# MainPCB.net
KiCad netlist of a schematic drawn in Altium Designer
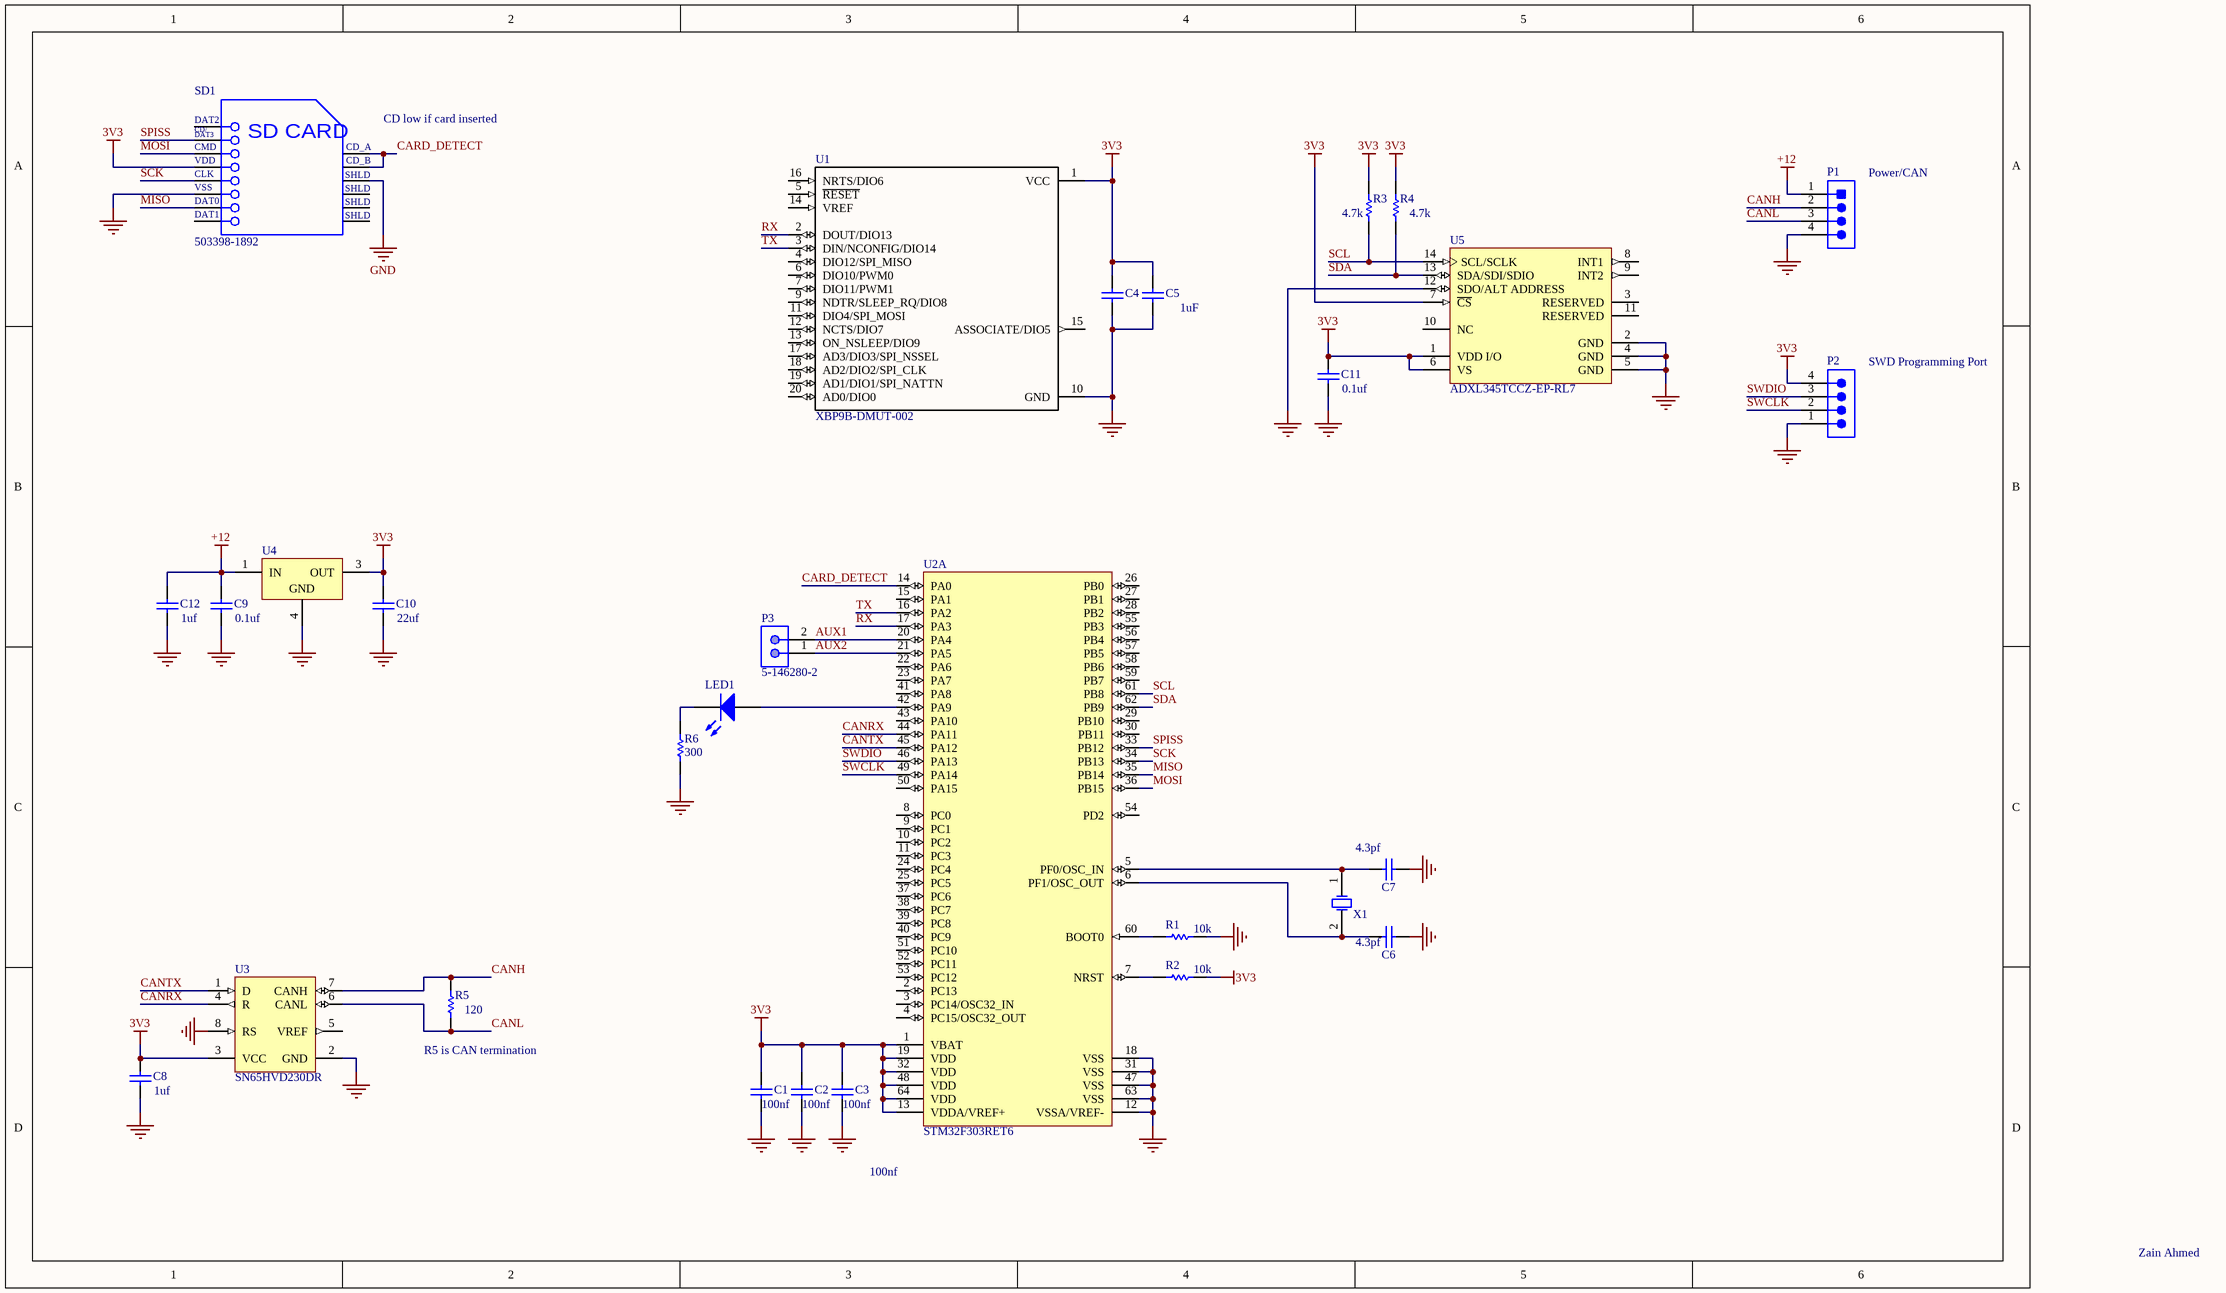
[diagram p0: MainPCB.SchDoc]

(export (version "E")
  (design (tool "Eeschema 10.0.6"))
  (components
    (comp (ref "C1")
      (value "C0402C104K8PAC7867")
      (footprint "CAPC1005X60X30ML05T10")
      (fields (field (name "MANUFACTURER") "Kemet"))
      (libsource (lib "Altium Content Vault") (part "CAP"))
    )
    (comp (ref "C2")
      (value "C0402C104K8PAC7867")
      (footprint "CAPC1005X60X30ML05T10")
      (fields (field (name "MANUFACTURER") "Kemet"))
      (libsource (lib "Altium Content Vault") (part "CAP"))
    )
    (comp (ref "C3")
      (value "C0402C104K8PAC7867")
      (footprint "CAPC1005X60X30ML05T10")
      (fields (field (name "MANUFACTURER") "Kemet"))
      (libsource (lib "Altium Content Vault") (part "CAP"))
    )
    (comp (ref "C4")
      (value "12065C105KAT2A")
      (footprint "CAPC3216X180X50LL20T25")
      (description "Chip Capacitor, 1 uF, +/- 10%, 50 V, -55 to 125 degC, 1206 (3216 Metric), RoHS, Tape and Reel")
      (fields (field (name "MANUFACTURER") "AVX"))
      (libsource (lib "Altium Content Vault") (part "CAP-NP-2"))
    )
    (comp (ref "C5")
      (value "12065C105KAT2A")
      (footprint "CAPC3216X180X50LL20T25")
      (description "Chip Capacitor, 1 uF, +/- 10%, 50 V, -55 to 125 degC, 1206 (3216 Metric), RoHS, Tape and Reel")
      (fields (field (name "MANUFACTURER") "AVX"))
      (libsource (lib "Altium Content Vault") (part "CAP-NP-2"))
    )
    (comp (ref "C6")
      (value "CAP 4.3pF 50V 0402(1005)")
      (footprint "CAPC0402(1005)60_M")
      (description "CAP 4.3pF 50V ±0.25pF 0402 (1005 Metric) Thickness 0.6mm SMD")
      (fields (field (name "TOLERANCE") "Â±0.25pF"))
      (libsource (lib "Altium Content Vault") (part "CAP"))
    )
    (comp (ref "C7")
      (value "CAP 4.3pF 50V 0402(1005)")
      (footprint "CAPC0402(1005)60_M")
      (description "CAP 4.3pF 50V ±0.25pF 0402 (1005 Metric) Thickness 0.6mm SMD")
      (fields (field (name "TOLERANCE") "Â±0.25pF"))
      (libsource (lib "Altium Content Vault") (part "CAP"))
    )
    (comp (ref "C8")
      (value "C1206C105K3RACTU")
      (footprint "CAPC3216X180X50ML20T25")
      (description "Chip Capacitor, 1 uF, +/- 10%, 25 V, -55 to 125 degC, 1206 (3216 Metric), RoHS, Tape and Reel")
      (fields (field (name "MANUFACTURER") "Kemet") (field (name "TOLERANCE") "10%"))
      (libsource (lib "Altium Content Vault") (part "CAP-NP-2"))
    )
    (comp (ref "C9")
      (value "GRM188R71H104KA93D")
      (footprint "CAPC1608X90X35ML10T15")
      (description "Chip Capacitor, 0.1 uF, +/- 10%, 50 V, -55 to 125 degC, 0603 (1608 Metric), RoHS, Tape and Reel")
      (fields (field (name "TOLERANCE") "10%") (field (name "VOLTAGE") "50V"))
      (libsource (lib "Altium Content Vault") (part "CAP-NP-2"))
    )
    (comp (ref "C10")
      (value "GRM188R61A226ME15D")
      (footprint "CAPC1608X100X38LL20T18")
      (description "Chip Capacitor, 22 uF, +/- 20%, 10 V, -55 to 85 degC, 0603 (1608 Metric), RoHS, Tape and Reel")
      (fields (field (name "MANUFACTURER") "Murata") (field (name "TOLERANCE") "20%"))
      (libsource (lib "Altium Content Vault") (part "CAP-NP-2"))
    )
    (comp (ref "C11")
      (value "GRM188R71H104KA93D")
      (footprint "CAPC1608X90X35ML10T15")
      (description "Chip Capacitor, 0.1 uF, +/- 10%, 50 V, -55 to 125 degC, 0603 (1608 Metric), RoHS, Tape and Reel")
      (fields (field (name "TOLERANCE") "10%") (field (name "VOLTAGE") "50V"))
      (libsource (lib "Altium Content Vault") (part "CAP-NP-2"))
    )
    (comp (ref "C12")
      (value "GRM155R61A105KE15D")
      (footprint "CAPC1005X55X25NL05T10")
      (fields (field (name "MANUFACTURER") "Murata"))
      (libsource (lib "Altium Content Vault") (part "CAP"))
    )
    (comp (ref "LED1")
      (value "150120BS75000")
      (footprint "1206_A")
      (description "SMD mono-color Chip LED, WL-SMCW, Blue")
      (fields (field (name "MANUFACTURER") "Wuerth Elektronik"))
      (libsource (lib "Altium Content Vault") (part "WE-LED_K1A2-2"))
    )
    (comp (ref "P1")
      (value "B4B-PH-K-S(LF)(SN)")
      (footprint "JST-B4B-PH-K-S_V")
      (fields (field (name "MANUFACTURER") "JST"))
      (libsource (lib "Altium Content Vault") (part "CN-1P-M-R4"))
    )
    (comp (ref "P2")
      (value "TSW-104-08-T-S")
      (footprint "SMTC-TSW-104-08-X-S")
      (description "0.025\" SQ Post Header, Through-hole, Vertical, -55 to 105 degC, 2.54 mm Pitch, 4-Pin, Male, RoHS")
      (fields (field (name "MANUFACTURER") "Samtec"))
      (libsource (lib "Altium Content Vault") (part "SMTC-TSW-104-08-X-S"))
    )
    (comp (ref "P3")
      (value "5-146280-2")
      (footprint "TECO-5-146280-2_V")
      (fields (field (name "MANUFACTURER") "TE Connectivity"))
      (libsource (lib "Altium Content Vault") (part "CN-1P-M-R2"))
    )
    (comp (ref "R1")
      (value "ERA8AEB103V")
      (footprint "RESC3216X70X50LL20T25")
      (fields (field (name "MANUFACTURER") "Panasonic"))
      (libsource (lib "Altium Content Vault") (part "RES"))
    )
    (comp (ref "R2")
      (value "ERA8AEB103V")
      (footprint "RESC3216X70X50LL20T25")
      (fields (field (name "MANUFACTURER") "Panasonic"))
      (libsource (lib "Altium Content Vault") (part "RES"))
    )
    (comp (ref "R3")
      (value "ERA6AEB472V")
      (footprint "RESC2013X60X40ML20T25")
      (fields (field (name "MANUFACTURER") "Panasonic"))
      (libsource (lib "Altium Content Vault") (part "RES"))
    )
    (comp (ref "R4")
      (value "ERA6AEB472V")
      (footprint "RESC2013X60X40ML20T25")
      (fields (field (name "MANUFACTURER") "Panasonic"))
      (libsource (lib "Altium Content Vault") (part "RES"))
    )
    (comp (ref "R5")
      (value "CRCW1206120RFKEA")
      (footprint "RESC3216X60X45LL10T20")
      (fields (field (name "MANUFACTURER") "Vishay Dale"))
      (libsource (lib "Altium Content Vault") (part "RES"))
    )
    (comp (ref "R6")
      (value "300")
      (footprint "RESC3216X70X50NL05T20")
      (fields (field (name "MANUFACTURER") "Panasonic") (field (name "PART NUMBER") "ERJ8ENF3000V"))
      (libsource (lib "Altium Content Vault") (part "RES"))
    )
    (comp (ref "SD1")
      (value "503398-1892")
      (footprint "MOLX-503398-1892_V")
      (description "Micro SD Connector, Pitch 1.1 mm, 8 Position, Height 1.4 mm, -25 to 85 degC, RoHS, Tape and Reel")
      (fields (field (name "MANUFACTURER") "Molex"))
      (libsource (lib "Altium Content Vault") (part "CN-SD-8-2SW-4S"))
    )
    (comp (ref "U1")
      (value "XBP9B-DMUT-002")
      (footprint "*DIP2200W51P200L3294H279Q20P")
      (description "XBee-PRO 900HP DigiMesh 900 MHz 200 Kbps RF Module with U.FL Connector")
      (fields (field (name "MF") "Digi International"))
      (libsource (lib "XBP9B-DMUT-002") (part "XBP9B-DMUT-002"))
    )
    (comp (ref "U2A")
      (value "STM32F303RET6")
      (footprint "STM-LQFP64_L")
      (libsource (lib "Altium Content Vault") (part "MC-ARM-STM32F303-LQFP64"))
    )
    (comp (ref "U3")
      (value "SN65HVD230DR")
      (footprint "D0008A_L")
      (fields (field (name "MANUFACTURER") "Texas Instruments"))
      (libsource (lib "Altium Content Vault") (part "TI-SN65HVD230-SOIC_D-8"))
    )
    (comp (ref "U4")
      (value "TL760M33QKVURQ1")
      (footprint "KVU0003A_M")
      (fields (field (name "MANUFACTURER") "Texas Instruments"))
      (libsource (lib "Altium Content Vault") (part "TI-TL7X0MXX-Q1KVU3"))
    )
    (comp (ref "U5")
      (value "ADXL345TCCZ-EP-RL7")
      (footprint "ADI-CC-14-1_V")
      (fields (field (name "MANUFACTURER") "Analog Devices"))
      (libsource (lib "Altium Content Vault") (part "ADI-ADXL34X-CC-14-1"))
    )
    (comp (ref "X1")
      (value "ABM3-8.000MHZ-D2Y-T")
      (footprint "ABRA-ABM3-2_V")
      (description "Miniature Ceramic Crystal, 8 MHz, -40 to 85 degC, 2-Pin SMD, RoHS, Tape and Reel")
      (fields (field (name "MANUFACTURER") "ABRACON") (field (name "TOLERANCE") "20PPM"))
      (libsource (lib "Altium Content Vault") (part "XTAL_1-2-2"))
    )
  )
  (nets
    (net (code "1") (name "+12") (class "Default")
      (node (ref "C12") (pin "1") (pinfunction "1_1") (pintype "passive"))
      (node (ref "C9") (pin "1") (pinfunction "1_1") (pintype "passive"))
      (node (ref "P1") (pin "1") (pinfunction "1_1") (pintype "passive"))
      (node (ref "U4") (pin "1") (pinfunction "IN_1") (pintype "power_in"))
    )
    (net (code "2") (name "/AUX1") (class "Default")
      (node (ref "P3") (pin "2") (pinfunction "2_2") (pintype "passive"))
      (node (ref "U2A") (pin "20") (pinfunction "PA4_20") (pintype "bidirectional"))
    )
    (net (code "3") (name "/AUX2") (class "Default")
      (node (ref "P3") (pin "1") (pinfunction "1_1") (pintype "passive"))
      (node (ref "U2A") (pin "21") (pinfunction "PA5_21") (pintype "bidirectional"))
    )
    (net (code "4") (name "/CANH") (class "Default")
      (node (ref "P1") (pin "2") (pinfunction "2_2") (pintype "passive"))
      (node (ref "R5") (pin "1") (pinfunction "1_1") (pintype "passive"))
      (node (ref "U3") (pin "7") (pinfunction "CANH_7") (pintype "bidirectional"))
    )
    (net (code "5") (name "/CANL") (class "Default")
      (node (ref "P1") (pin "3") (pinfunction "3_3") (pintype "passive"))
      (node (ref "R5") (pin "2") (pinfunction "2_2") (pintype "passive"))
      (node (ref "U3") (pin "6") (pinfunction "CANL_6") (pintype "bidirectional"))
    )
    (net (code "6") (name "/CANRX") (class "Default")
      (node (ref "U2A") (pin "44") (pinfunction "PA11_44") (pintype "bidirectional"))
      (node (ref "U3") (pin "4") (pinfunction "R_4") (pintype "output"))
    )
    (net (code "7") (name "/CANTX") (class "Default")
      (node (ref "U2A") (pin "45") (pinfunction "PA12_45") (pintype "bidirectional"))
      (node (ref "U3") (pin "1") (pinfunction "D_1") (pintype "input"))
    )
    (net (code "8") (name "/CARD_DETECT") (class "Default")
      (node (ref "SD1") (pin "10") (pinfunction "CD_B_10") (pintype "passive"))
      (node (ref "SD1") (pin "9") (pinfunction "CD_A_9") (pintype "passive"))
      (node (ref "U2A") (pin "14") (pinfunction "PA0_14") (pintype "bidirectional"))
    )
    (net (code "9") (name "/MISO") (class "Default")
      (node (ref "SD1") (pin "7") (pinfunction "DAT0_7") (pintype "passive"))
      (node (ref "U2A") (pin "35") (pinfunction "PB14_35") (pintype "bidirectional"))
    )
    (net (code "10") (name "/MOSI") (class "Default")
      (node (ref "SD1") (pin "3") (pinfunction "CMD_3") (pintype "passive"))
      (node (ref "U2A") (pin "36") (pinfunction "PB15_36") (pintype "bidirectional"))
    )
    (net (code "11") (name "/RX") (class "Default")
      (node (ref "U1") (pin "2") (pinfunction "DOUT/DIO13_2") (pintype "bidirectional"))
      (node (ref "U2A") (pin "17") (pinfunction "PA3_17") (pintype "bidirectional"))
    )
    (net (code "12") (name "/SCK") (class "Default")
      (node (ref "SD1") (pin "5") (pinfunction "CLK_5") (pintype "passive"))
      (node (ref "U2A") (pin "34") (pinfunction "PB13_34") (pintype "bidirectional"))
    )
    (net (code "13") (name "/SCL") (class "Default")
      (node (ref "R3") (pin "2") (pinfunction "2_2") (pintype "passive"))
      (node (ref "U2A") (pin "61") (pinfunction "PB8_61") (pintype "bidirectional"))
      (node (ref "U5") (pin "14") (pinfunction "SCL/SCLK_14") (pintype "input"))
    )
    (net (code "14") (name "/SDA") (class "Default")
      (node (ref "R4") (pin "2") (pinfunction "2_2") (pintype "passive"))
      (node (ref "U2A") (pin "62") (pinfunction "PB9_62") (pintype "bidirectional"))
      (node (ref "U5") (pin "13") (pinfunction "SDA/SDI/SDIO_13") (pintype "bidirectional"))
    )
    (net (code "15") (name "/SPISS") (class "Default")
      (node (ref "SD1") (pin "2") (pinfunction "CD/DAT3_2") (pintype "passive"))
      (node (ref "U2A") (pin "33") (pinfunction "PB12_33") (pintype "bidirectional"))
    )
    (net (code "16") (name "/SWCLK") (class "Default")
      (node (ref "P2") (pin "2") (pinfunction "2_2") (pintype "passive"))
      (node (ref "U2A") (pin "49") (pinfunction "PA14_49") (pintype "bidirectional"))
    )
    (net (code "17") (name "/SWDIO") (class "Default")
      (node (ref "P2") (pin "3") (pinfunction "3_3") (pintype "passive"))
      (node (ref "U2A") (pin "46") (pinfunction "PA13_46") (pintype "bidirectional"))
    )
    (net (code "18") (name "/TX") (class "Default")
      (node (ref "U1") (pin "3") (pinfunction "DIN/NCONFIG/DIO14_3") (pintype "bidirectional"))
      (node (ref "U2A") (pin "16") (pinfunction "PA2_16") (pintype "bidirectional"))
    )
    (net (code "19") (name "3V3") (class "Default")
      (node (ref "C1") (pin "1") (pinfunction "1_1") (pintype "passive"))
      (node (ref "C10") (pin "1") (pinfunction "1_1") (pintype "passive"))
      (node (ref "C11") (pin "1") (pinfunction "1_1") (pintype "passive"))
      (node (ref "C2") (pin "1") (pinfunction "1_1") (pintype "passive"))
      (node (ref "C3") (pin "1") (pinfunction "1_1") (pintype "passive"))
      (node (ref "C4") (pin "1") (pinfunction "1_1") (pintype "passive"))
      (node (ref "C5") (pin "1") (pinfunction "1_1") (pintype "passive"))
      (node (ref "C8") (pin "1") (pinfunction "1_1") (pintype "passive"))
      (node (ref "P2") (pin "4") (pinfunction "4_4") (pintype "passive"))
      (node (ref "R2") (pin "2") (pinfunction "2_2") (pintype "passive"))
      (node (ref "R3") (pin "1") (pinfunction "1_1") (pintype "passive"))
      (node (ref "R4") (pin "1") (pinfunction "1_1") (pintype "passive"))
      (node (ref "SD1") (pin "4") (pinfunction "VDD_4") (pintype "passive"))
      (node (ref "U1") (pin "1") (pinfunction "VCC_1") (pintype "power_in"))
      (node (ref "U2A") (pin "1") (pinfunction "VBAT_1") (pintype "power_in"))
      (node (ref "U2A") (pin "13") (pinfunction "VDDA/VREF+_13") (pintype "power_in"))
      (node (ref "U2A") (pin "19") (pinfunction "VDD_19") (pintype "power_in"))
      (node (ref "U2A") (pin "32") (pinfunction "VDD_32") (pintype "power_in"))
      (node (ref "U2A") (pin "48") (pinfunction "VDD_48") (pintype "power_in"))
      (node (ref "U2A") (pin "64") (pinfunction "VDD_64") (pintype "power_in"))
      (node (ref "U3") (pin "3") (pinfunction "VCC_3") (pintype "power_in"))
      (node (ref "U4") (pin "3") (pinfunction "OUT_3") (pintype "power_in"))
      (node (ref "U5") (pin "1") (pinfunction "VDD_I/O_1") (pintype "power_in"))
      (node (ref "U5") (pin "6") (pinfunction "VS_6") (pintype "power_in"))
      (node (ref "U5") (pin "7") (pinfunction "~{CS}_7") (pintype "input"))
    )
    (net (code "20") (name "GND") (class "Default")
      (node (ref "C1") (pin "2") (pinfunction "2_2") (pintype "passive"))
      (node (ref "C10") (pin "2") (pinfunction "2_2") (pintype "passive"))
      (node (ref "C11") (pin "2") (pinfunction "2_2") (pintype "passive"))
      (node (ref "C12") (pin "2") (pinfunction "2_2") (pintype "passive"))
      (node (ref "C2") (pin "2") (pinfunction "2_2") (pintype "passive"))
      (node (ref "C3") (pin "2") (pinfunction "2_2") (pintype "passive"))
      (node (ref "C4") (pin "2") (pinfunction "2_2") (pintype "passive"))
      (node (ref "C5") (pin "2") (pinfunction "2_2") (pintype "passive"))
      (node (ref "C6") (pin "1") (pinfunction "1_1") (pintype "passive"))
      (node (ref "C7") (pin "1") (pinfunction "1_1") (pintype "passive"))
      (node (ref "C8") (pin "2") (pinfunction "2_2") (pintype "passive"))
      (node (ref "C9") (pin "2") (pinfunction "2_2") (pintype "passive"))
      (node (ref "P1") (pin "4") (pinfunction "4_4") (pintype "passive"))
      (node (ref "P2") (pin "1") (pinfunction "1_1") (pintype "passive"))
      (node (ref "R1") (pin "2") (pinfunction "2_2") (pintype "passive"))
      (node (ref "R6") (pin "2") (pinfunction "2_2") (pintype "passive"))
      (node (ref "SD1") (pin "11") (pinfunction "SHLD_11") (pintype "passive"))
      (node (ref "SD1") (pin "6") (pinfunction "VSS_6") (pintype "passive"))
      (node (ref "U1") (pin "10") (pinfunction "GND_10") (pintype "power_in"))
      (node (ref "U2A") (pin "12") (pinfunction "VSSA/VREF-_12") (pintype "power_in"))
      (node (ref "U2A") (pin "18") (pinfunction "VSS_18") (pintype "power_in"))
      (node (ref "U2A") (pin "31") (pinfunction "VSS_31") (pintype "power_in"))
      (node (ref "U2A") (pin "47") (pinfunction "VSS_47") (pintype "power_in"))
      (node (ref "U2A") (pin "63") (pinfunction "VSS_63") (pintype "power_in"))
      (node (ref "U3") (pin "2") (pinfunction "GND_2") (pintype "power_in"))
      (node (ref "U3") (pin "8") (pinfunction "RS_8") (pintype "input"))
      (node (ref "U4") (pin "4") (pinfunction "GND_4") (pintype "power_in"))
      (node (ref "U5") (pin "12") (pinfunction "SDO/ALT_ADDRESS_12") (pintype "bidirectional"))
      (node (ref "U5") (pin "2") (pinfunction "GND_2") (pintype "power_in"))
      (node (ref "U5") (pin "4") (pinfunction "GND_4") (pintype "power_in"))
      (node (ref "U5") (pin "5") (pinfunction "GND_5") (pintype "power_in"))
    )
    (net (code "21") (name "Net-(LED1-A)") (class "Default")
      (node (ref "LED1") (pin "2") (pinfunction "A_2") (pintype "passive"))
      (node (ref "U2A") (pin "42") (pinfunction "PA9_42") (pintype "bidirectional"))
    )
    (net (code "22") (name "Net-(LED1-K)") (class "Default")
      (node (ref "LED1") (pin "1") (pinfunction "K_1") (pintype "passive"))
      (node (ref "R6") (pin "1") (pinfunction "1_1") (pintype "passive"))
    )
    (net (code "23") (name "Net-(U2A-BOOT0)") (class "Default")
      (node (ref "R1") (pin "1") (pinfunction "1_1") (pintype "passive"))
      (node (ref "U2A") (pin "60") (pinfunction "BOOT0_60") (pintype "input"))
    )
    (net (code "24") (name "Net-(U2A-NRST)") (class "Default")
      (node (ref "R2") (pin "1") (pinfunction "1_1") (pintype "passive"))
      (node (ref "U2A") (pin "7") (pinfunction "NRST_7") (pintype "bidirectional"))
    )
    (net (code "25") (name "Net-(U2A-PF0{slash}OSC_IN)") (class "Default")
      (node (ref "C7") (pin "2") (pinfunction "2_2") (pintype "passive"))
      (node (ref "U2A") (pin "5") (pinfunction "PF0/OSC_IN_5") (pintype "bidirectional"))
      (node (ref "X1") (pin "1") (pinfunction "X1_1") (pintype "passive"))
    )
    (net (code "26") (name "Net-(U2A-PF1{slash}OSC_OUT)") (class "Default")
      (node (ref "C6") (pin "2") (pinfunction "2_2") (pintype "passive"))
      (node (ref "U2A") (pin "6") (pinfunction "PF1/OSC_OUT_6") (pintype "bidirectional"))
      (node (ref "X1") (pin "2") (pinfunction "X2_2") (pintype "passive"))
    )
    (net (code "27") (name "unconnected-(SD1-DAT1-Pad8)") (class "Default")
      (node (ref "SD1") (pin "8") (pinfunction "DAT1_8") (pintype "passive"))
    )
    (net (code "28") (name "unconnected-(SD1-DAT2-Pad1)") (class "Default")
      (node (ref "SD1") (pin "1") (pinfunction "DAT2_1") (pintype "passive"))
    )
    (net (code "29") (name "unconnected-(SD1-SHLD-Pad12)") (class "Default")
      (node (ref "SD1") (pin "12") (pinfunction "SHLD_12") (pintype "passive"))
    )
    (net (code "30") (name "unconnected-(SD1-SHLD-Pad13)") (class "Default")
      (node (ref "SD1") (pin "13") (pinfunction "SHLD_13") (pintype "passive"))
    )
    (net (code "31") (name "unconnected-(SD1-SHLD-Pad14)") (class "Default")
      (node (ref "SD1") (pin "14") (pinfunction "SHLD_14") (pintype "passive"))
    )
    (net (code "32") (name "unconnected-(U1-AD0{slash}DIO0-Pad20)") (class "Default")
      (node (ref "U1") (pin "20") (pinfunction "AD0/DIO0_20") (pintype "bidirectional"))
    )
    (net (code "33") (name "unconnected-(U1-AD1{slash}DIO1{slash}SPI_NATTN-Pad19)") (class "Default")
      (node (ref "U1") (pin "19") (pinfunction "AD1/DIO1/SPI_NATTN_19") (pintype "bidirectional"))
    )
    (net (code "34") (name "unconnected-(U1-AD2{slash}DIO2{slash}SPI_CLK-Pad18)") (class "Default")
      (node (ref "U1") (pin "18") (pinfunction "AD2/DIO2/SPI_CLK_18") (pintype "bidirectional"))
    )
    (net (code "35") (name "unconnected-(U1-AD3{slash}DIO3{slash}SPI_NSSEL-Pad17)") (class "Default")
      (node (ref "U1") (pin "17") (pinfunction "AD3/DIO3/SPI_NSSEL_17") (pintype "bidirectional"))
    )
    (net (code "36") (name "unconnected-(U1-ASSOCIATE{slash}DIO5-Pad15)") (class "Default")
      (node (ref "U1") (pin "15") (pinfunction "ASSOCIATE/DIO5_15") (pintype "output"))
    )
    (net (code "37") (name "unconnected-(U1-DIO4{slash}SPI_MOSI-Pad11)") (class "Default")
      (node (ref "U1") (pin "11") (pinfunction "DIO4/SPI_MOSI_11") (pintype "bidirectional"))
    )
    (net (code "38") (name "unconnected-(U1-DIO10{slash}PWM0-Pad6)") (class "Default")
      (node (ref "U1") (pin "6") (pinfunction "DIO10/PWM0_6") (pintype "bidirectional"))
    )
    (net (code "39") (name "unconnected-(U1-DIO11{slash}PWM1-Pad7)") (class "Default")
      (node (ref "U1") (pin "7") (pinfunction "DIO11/PWM1_7") (pintype "bidirectional"))
    )
    (net (code "40") (name "unconnected-(U1-DIO12{slash}SPI_MISO-Pad4)") (class "Default")
      (node (ref "U1") (pin "4") (pinfunction "DIO12/SPI_MISO_4") (pintype "bidirectional"))
    )
    (net (code "41") (name "unconnected-(U1-NCTS{slash}DIO7-Pad12)") (class "Default")
      (node (ref "U1") (pin "12") (pinfunction "NCTS/DIO7_12") (pintype "bidirectional"))
    )
    (net (code "42") (name "unconnected-(U1-NDTR{slash}SLEEP_RQ{slash}DIO8-Pad9)") (class "Default")
      (node (ref "U1") (pin "9") (pinfunction "NDTR/SLEEP_RQ/DIO8_9") (pintype "bidirectional"))
    )
    (net (code "43") (name "unconnected-(U1-NRTS{slash}DIO6-Pad16)") (class "Default")
      (node (ref "U1") (pin "16") (pinfunction "NRTS/DIO6_16") (pintype "input"))
    )
    (net (code "44") (name "unconnected-(U1-ON_NSLEEP{slash}DIO9-Pad13)") (class "Default")
      (node (ref "U1") (pin "13") (pinfunction "ON_NSLEEP/DIO9_13") (pintype "bidirectional"))
    )
    (net (code "45") (name "unconnected-(U1-VREF-Pad14)") (class "Default")
      (node (ref "U1") (pin "14") (pinfunction "VREF_14") (pintype "input"))
    )
    (net (code "46") (name "unconnected-(U1-~{RESET}-Pad5)") (class "Default")
      (node (ref "U1") (pin "5") (pinfunction "~{RESET}_5") (pintype "input"))
    )
    (net (code "47") (name "unconnected-(U2A-PA1-Pad15)") (class "Default")
      (node (ref "U2A") (pin "15") (pinfunction "PA1_15") (pintype "bidirectional"))
    )
    (net (code "48") (name "unconnected-(U2A-PA6-Pad22)") (class "Default")
      (node (ref "U2A") (pin "22") (pinfunction "PA6_22") (pintype "bidirectional"))
    )
    (net (code "49") (name "unconnected-(U2A-PA7-Pad23)") (class "Default")
      (node (ref "U2A") (pin "23") (pinfunction "PA7_23") (pintype "bidirectional"))
    )
    (net (code "50") (name "unconnected-(U2A-PA8-Pad41)") (class "Default")
      (node (ref "U2A") (pin "41") (pinfunction "PA8_41") (pintype "bidirectional"))
    )
    (net (code "51") (name "unconnected-(U2A-PA10-Pad43)") (class "Default")
      (node (ref "U2A") (pin "43") (pinfunction "PA10_43") (pintype "bidirectional"))
    )
    (net (code "52") (name "unconnected-(U2A-PA15-Pad50)") (class "Default")
      (node (ref "U2A") (pin "50") (pinfunction "PA15_50") (pintype "bidirectional"))
    )
    (net (code "53") (name "unconnected-(U2A-PB0-Pad26)") (class "Default")
      (node (ref "U2A") (pin "26") (pinfunction "PB0_26") (pintype "bidirectional"))
    )
    (net (code "54") (name "unconnected-(U2A-PB1-Pad27)") (class "Default")
      (node (ref "U2A") (pin "27") (pinfunction "PB1_27") (pintype "bidirectional"))
    )
    (net (code "55") (name "unconnected-(U2A-PB2-Pad28)") (class "Default")
      (node (ref "U2A") (pin "28") (pinfunction "PB2_28") (pintype "bidirectional"))
    )
    (net (code "56") (name "unconnected-(U2A-PB3-Pad55)") (class "Default")
      (node (ref "U2A") (pin "55") (pinfunction "PB3_55") (pintype "bidirectional"))
    )
    (net (code "57") (name "unconnected-(U2A-PB4-Pad56)") (class "Default")
      (node (ref "U2A") (pin "56") (pinfunction "PB4_56") (pintype "bidirectional"))
    )
    (net (code "58") (name "unconnected-(U2A-PB5-Pad57)") (class "Default")
      (node (ref "U2A") (pin "57") (pinfunction "PB5_57") (pintype "bidirectional"))
    )
    (net (code "59") (name "unconnected-(U2A-PB6-Pad58)") (class "Default")
      (node (ref "U2A") (pin "58") (pinfunction "PB6_58") (pintype "bidirectional"))
    )
    (net (code "60") (name "unconnected-(U2A-PB7-Pad59)") (class "Default")
      (node (ref "U2A") (pin "59") (pinfunction "PB7_59") (pintype "bidirectional"))
    )
    (net (code "61") (name "unconnected-(U2A-PB10-Pad29)") (class "Default")
      (node (ref "U2A") (pin "29") (pinfunction "PB10_29") (pintype "bidirectional"))
    )
    (net (code "62") (name "unconnected-(U2A-PB11-Pad30)") (class "Default")
      (node (ref "U2A") (pin "30") (pinfunction "PB11_30") (pintype "bidirectional"))
    )
    (net (code "63") (name "unconnected-(U2A-PC0-Pad8)") (class "Default")
      (node (ref "U2A") (pin "8") (pinfunction "PC0_8") (pintype "bidirectional"))
    )
    (net (code "64") (name "unconnected-(U2A-PC1-Pad9)") (class "Default")
      (node (ref "U2A") (pin "9") (pinfunction "PC1_9") (pintype "bidirectional"))
    )
    (net (code "65") (name "unconnected-(U2A-PC2-Pad10)") (class "Default")
      (node (ref "U2A") (pin "10") (pinfunction "PC2_10") (pintype "bidirectional"))
    )
    (net (code "66") (name "unconnected-(U2A-PC3-Pad11)") (class "Default")
      (node (ref "U2A") (pin "11") (pinfunction "PC3_11") (pintype "bidirectional"))
    )
    (net (code "67") (name "unconnected-(U2A-PC4-Pad24)") (class "Default")
      (node (ref "U2A") (pin "24") (pinfunction "PC4_24") (pintype "bidirectional"))
    )
    (net (code "68") (name "unconnected-(U2A-PC5-Pad25)") (class "Default")
      (node (ref "U2A") (pin "25") (pinfunction "PC5_25") (pintype "bidirectional"))
    )
    (net (code "69") (name "unconnected-(U2A-PC6-Pad37)") (class "Default")
      (node (ref "U2A") (pin "37") (pinfunction "PC6_37") (pintype "bidirectional"))
    )
    (net (code "70") (name "unconnected-(U2A-PC7-Pad38)") (class "Default")
      (node (ref "U2A") (pin "38") (pinfunction "PC7_38") (pintype "bidirectional"))
    )
    (net (code "71") (name "unconnected-(U2A-PC8-Pad39)") (class "Default")
      (node (ref "U2A") (pin "39") (pinfunction "PC8_39") (pintype "bidirectional"))
    )
    (net (code "72") (name "unconnected-(U2A-PC9-Pad40)") (class "Default")
      (node (ref "U2A") (pin "40") (pinfunction "PC9_40") (pintype "bidirectional"))
    )
    (net (code "73") (name "unconnected-(U2A-PC10-Pad51)") (class "Default")
      (node (ref "U2A") (pin "51") (pinfunction "PC10_51") (pintype "bidirectional"))
    )
    (net (code "74") (name "unconnected-(U2A-PC11-Pad52)") (class "Default")
      (node (ref "U2A") (pin "52") (pinfunction "PC11_52") (pintype "bidirectional"))
    )
    (net (code "75") (name "unconnected-(U2A-PC12-Pad53)") (class "Default")
      (node (ref "U2A") (pin "53") (pinfunction "PC12_53") (pintype "bidirectional"))
    )
    (net (code "76") (name "unconnected-(U2A-PC13-Pad2)") (class "Default")
      (node (ref "U2A") (pin "2") (pinfunction "PC13_2") (pintype "bidirectional"))
    )
    (net (code "77") (name "unconnected-(U2A-PC14{slash}OSC32_IN-Pad3)") (class "Default")
      (node (ref "U2A") (pin "3") (pinfunction "PC14/OSC32_IN_3") (pintype "bidirectional"))
    )
    (net (code "78") (name "unconnected-(U2A-PC15{slash}OSC32_OUT-Pad4)") (class "Default")
      (node (ref "U2A") (pin "4") (pinfunction "PC15/OSC32_OUT_4") (pintype "bidirectional"))
    )
    (net (code "79") (name "unconnected-(U2A-PD2-Pad54)") (class "Default")
      (node (ref "U2A") (pin "54") (pinfunction "PD2_54") (pintype "bidirectional"))
    )
    (net (code "80") (name "unconnected-(U3-VREF-Pad5)") (class "Default")
      (node (ref "U3") (pin "5") (pinfunction "VREF_5") (pintype "output"))
    )
    (net (code "81") (name "unconnected-(U5-INT1-Pad8)") (class "Default")
      (node (ref "U5") (pin "8") (pinfunction "INT1_8") (pintype "output"))
    )
    (net (code "82") (name "unconnected-(U5-INT2-Pad9)") (class "Default")
      (node (ref "U5") (pin "9") (pinfunction "INT2_9") (pintype "output"))
    )
    (net (code "83") (name "unconnected-(U5-NC-Pad10)") (class "Default")
      (node (ref "U5") (pin "10") (pinfunction "NC_10") (pintype "passive"))
    )
    (net (code "84") (name "unconnected-(U5-RESERVED-Pad3)") (class "Default")
      (node (ref "U5") (pin "3") (pinfunction "RESERVED_3") (pintype "passive"))
    )
    (net (code "85") (name "unconnected-(U5-RESERVED-Pad11)") (class "Default")
      (node (ref "U5") (pin "11") (pinfunction "RESERVED_11") (pintype "passive"))
    )
  )
)
